# EEGAmp_SMT_OPA4377.net
KiCad netlist of a schematic drawn in EAGLE
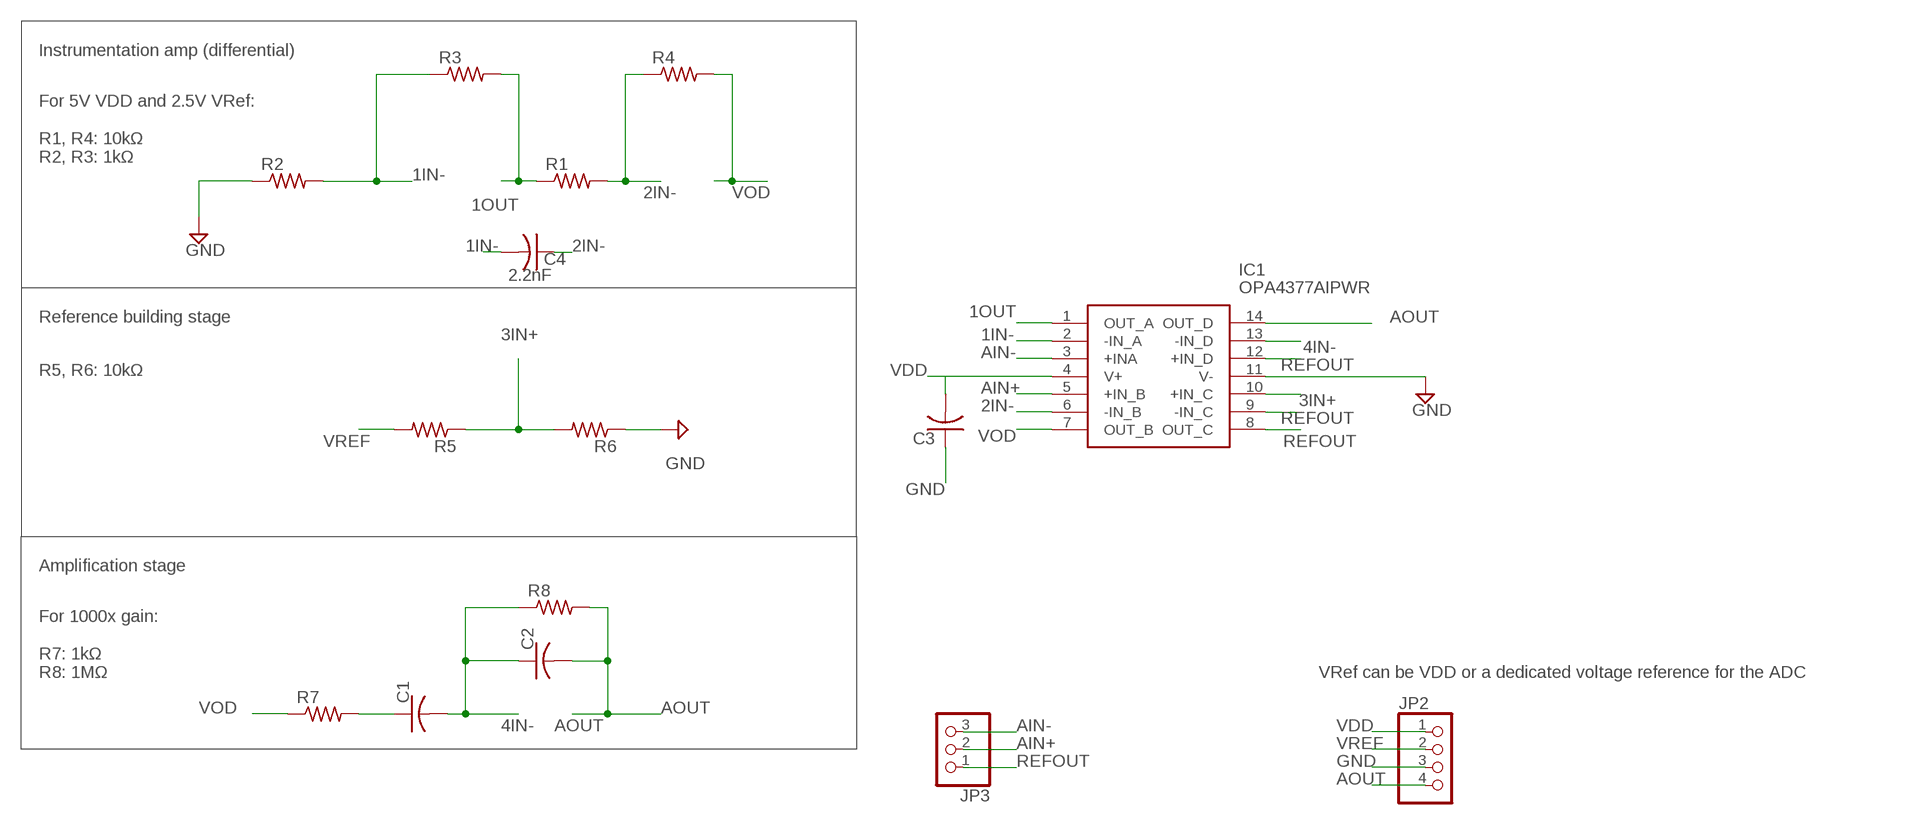
[diagram p0: schematic, sheet 1]

(export (version "E")
  (design (tool "Eeschema 10.0.6"))
  (components
    (comp (ref "C1")
      (value "C-USC0402")
      (footprint "eagle-import:C0402")
      (libsource (lib "eagle-import") (part "C-USC0402"))
    )
    (comp (ref "C2")
      (value "C-USC0402")
      (footprint "eagle-import:C0402")
      (libsource (lib "eagle-import") (part "C-USC0402"))
    )
    (comp (ref "C3")
      (value "C-USC0402")
      (footprint "eagle-import:C0402")
      (libsource (lib "eagle-import") (part "C-USC0402"))
    )
    (comp (ref "C4")
      (value "2.2nF")
      (footprint "eagle-import:C0402")
      (libsource (lib "eagle-import") (part "C-USC0402"))
    )
    (comp (ref "IC1")
      (value "OPA4377AIPWR")
      (footprint "eagle-import:SOP65P640X120-14N")
      (fields (field (name "MOUSER_PART_NUMBER") "595-OPA4377AIPWR"))
      (libsource (lib "eagle-import") (part "OPA4377AIPWR"))
    )
    (comp (ref "JP2")
      (value "PINHD-1X4")
      (footprint "eagle-import:1X04")
      (libsource (lib "eagle-import") (part "PINHD-1X4"))
    )
    (comp (ref "JP3")
      (value "PINHD-1X3")
      (footprint "eagle-import:1X03")
      (libsource (lib "eagle-import") (part "PINHD-1X3"))
    )
    (comp (ref "R1")
      (value "R-US_R0402")
      (footprint "eagle-import:R0402")
      (libsource (lib "eagle-import") (part "R-US_R0402"))
    )
    (comp (ref "R2")
      (value "R-US_R0402")
      (footprint "eagle-import:R0402")
      (libsource (lib "eagle-import") (part "R-US_R0402"))
    )
    (comp (ref "R3")
      (value "R-US_R0402")
      (footprint "eagle-import:R0402")
      (libsource (lib "eagle-import") (part "R-US_R0402"))
    )
    (comp (ref "R4")
      (value "R-US_R0402")
      (footprint "eagle-import:R0402")
      (libsource (lib "eagle-import") (part "R-US_R0402"))
    )
    (comp (ref "R5")
      (value "R-US_R0402")
      (footprint "eagle-import:R0402")
      (libsource (lib "eagle-import") (part "R-US_R0402"))
    )
    (comp (ref "R6")
      (value "R-US_R0402")
      (footprint "eagle-import:R0402")
      (libsource (lib "eagle-import") (part "R-US_R0402"))
    )
    (comp (ref "R7")
      (value "R-US_R0402")
      (footprint "eagle-import:R0402")
      (libsource (lib "eagle-import") (part "R-US_R0402"))
    )
    (comp (ref "R8")
      (value "R-US_R0402")
      (footprint "eagle-import:R0402")
      (libsource (lib "eagle-import") (part "R-US_R0402"))
    )
  )
  (nets
    (net (code "1") (name "/1IN-") (class "Default")
      (node (ref "C4") (pin "2") (pinfunction "2_2") (pintype "passive"))
      (node (ref "IC1") (pin "2") (pinfunction "-IN_A_2") (pintype "bidirectional"))
      (node (ref "R2") (pin "2") (pinfunction "2_2") (pintype "passive"))
      (node (ref "R3") (pin "1") (pinfunction "1_1") (pintype "passive"))
    )
    (net (code "2") (name "/1OUT") (class "Default")
      (node (ref "IC1") (pin "1") (pinfunction "OUT_A_1") (pintype "bidirectional"))
      (node (ref "R1") (pin "1") (pinfunction "1_1") (pintype "passive"))
      (node (ref "R3") (pin "2") (pinfunction "2_2") (pintype "passive"))
    )
    (net (code "3") (name "/2IN-") (class "Default")
      (node (ref "C4") (pin "1") (pinfunction "1_1") (pintype "passive"))
      (node (ref "IC1") (pin "6") (pinfunction "-IN_B_6") (pintype "bidirectional"))
      (node (ref "R1") (pin "2") (pinfunction "2_2") (pintype "passive"))
      (node (ref "R4") (pin "1") (pinfunction "1_1") (pintype "passive"))
    )
    (net (code "4") (name "/3IN+") (class "Default")
      (node (ref "IC1") (pin "10") (pinfunction "+IN_C_10") (pintype "bidirectional"))
      (node (ref "R5") (pin "1") (pinfunction "1_1") (pintype "passive"))
      (node (ref "R6") (pin "2") (pinfunction "2_2") (pintype "passive"))
    )
    (net (code "5") (name "/4IN-") (class "Default")
      (node (ref "C1") (pin "2") (pinfunction "2_2") (pintype "passive"))
      (node (ref "C2") (pin "1") (pinfunction "1_1") (pintype "passive"))
      (node (ref "IC1") (pin "13") (pinfunction "-IN_D_13") (pintype "bidirectional"))
      (node (ref "R8") (pin "1") (pinfunction "1_1") (pintype "passive"))
    )
    (net (code "6") (name "/AIN+") (class "Default")
      (node (ref "IC1") (pin "5") (pinfunction "+IN_B_5") (pintype "bidirectional"))
      (node (ref "JP3") (pin "2") (pinfunction "2_2") (pintype "passive"))
    )
    (net (code "7") (name "/AIN-") (class "Default")
      (node (ref "IC1") (pin "3") (pinfunction "+INA_3") (pintype "bidirectional"))
      (node (ref "JP3") (pin "3") (pinfunction "3_3") (pintype "passive"))
    )
    (net (code "8") (name "/AOUT") (class "Default")
      (node (ref "C2") (pin "2") (pinfunction "2_2") (pintype "passive"))
      (node (ref "IC1") (pin "14") (pinfunction "OUT_D_14") (pintype "bidirectional"))
      (node (ref "JP2") (pin "4") (pinfunction "4_4") (pintype "passive"))
      (node (ref "R8") (pin "2") (pinfunction "2_2") (pintype "passive"))
    )
    (net (code "9") (name "/REFOUT") (class "Default")
      (node (ref "IC1") (pin "12") (pinfunction "+IN_D_12") (pintype "bidirectional"))
      (node (ref "IC1") (pin "8") (pinfunction "OUT_C_8") (pintype "bidirectional"))
      (node (ref "IC1") (pin "9") (pinfunction "-IN_C_9") (pintype "bidirectional"))
      (node (ref "JP3") (pin "1") (pinfunction "1_1") (pintype "passive"))
    )
    (net (code "10") (name "/VDD") (class "Default")
      (node (ref "C3") (pin "2") (pinfunction "2_2") (pintype "passive"))
      (node (ref "IC1") (pin "4") (pinfunction "V+_4") (pintype "bidirectional"))
      (node (ref "JP2") (pin "1") (pinfunction "1_1") (pintype "passive"))
    )
    (net (code "11") (name "/VOD") (class "Default")
      (node (ref "IC1") (pin "7") (pinfunction "OUT_B_7") (pintype "bidirectional"))
      (node (ref "R4") (pin "2") (pinfunction "2_2") (pintype "passive"))
      (node (ref "R7") (pin "1") (pinfunction "1_1") (pintype "passive"))
    )
    (net (code "12") (name "/VREF") (class "Default")
      (node (ref "JP2") (pin "2") (pinfunction "2_2") (pintype "passive"))
      (node (ref "R5") (pin "2") (pinfunction "2_2") (pintype "passive"))
    )
    (net (code "13") (name "GND") (class "Default")
      (node (ref "C3") (pin "1") (pinfunction "1_1") (pintype "passive"))
      (node (ref "IC1") (pin "11") (pinfunction "V-_11") (pintype "bidirectional"))
      (node (ref "JP2") (pin "3") (pinfunction "3_3") (pintype "passive"))
      (node (ref "R2") (pin "1") (pinfunction "1_1") (pintype "passive"))
      (node (ref "R6") (pin "1") (pinfunction "1_1") (pintype "passive"))
    )
    (net (code "14") (name "Net-(C1-Pad1)") (class "Default")
      (node (ref "C1") (pin "1") (pinfunction "1_1") (pintype "passive"))
      (node (ref "R7") (pin "2") (pinfunction "2_2") (pintype "passive"))
    )
  )
)
